# HW_Lab.net
KiCad netlist of a schematic drawn in Altium Designer
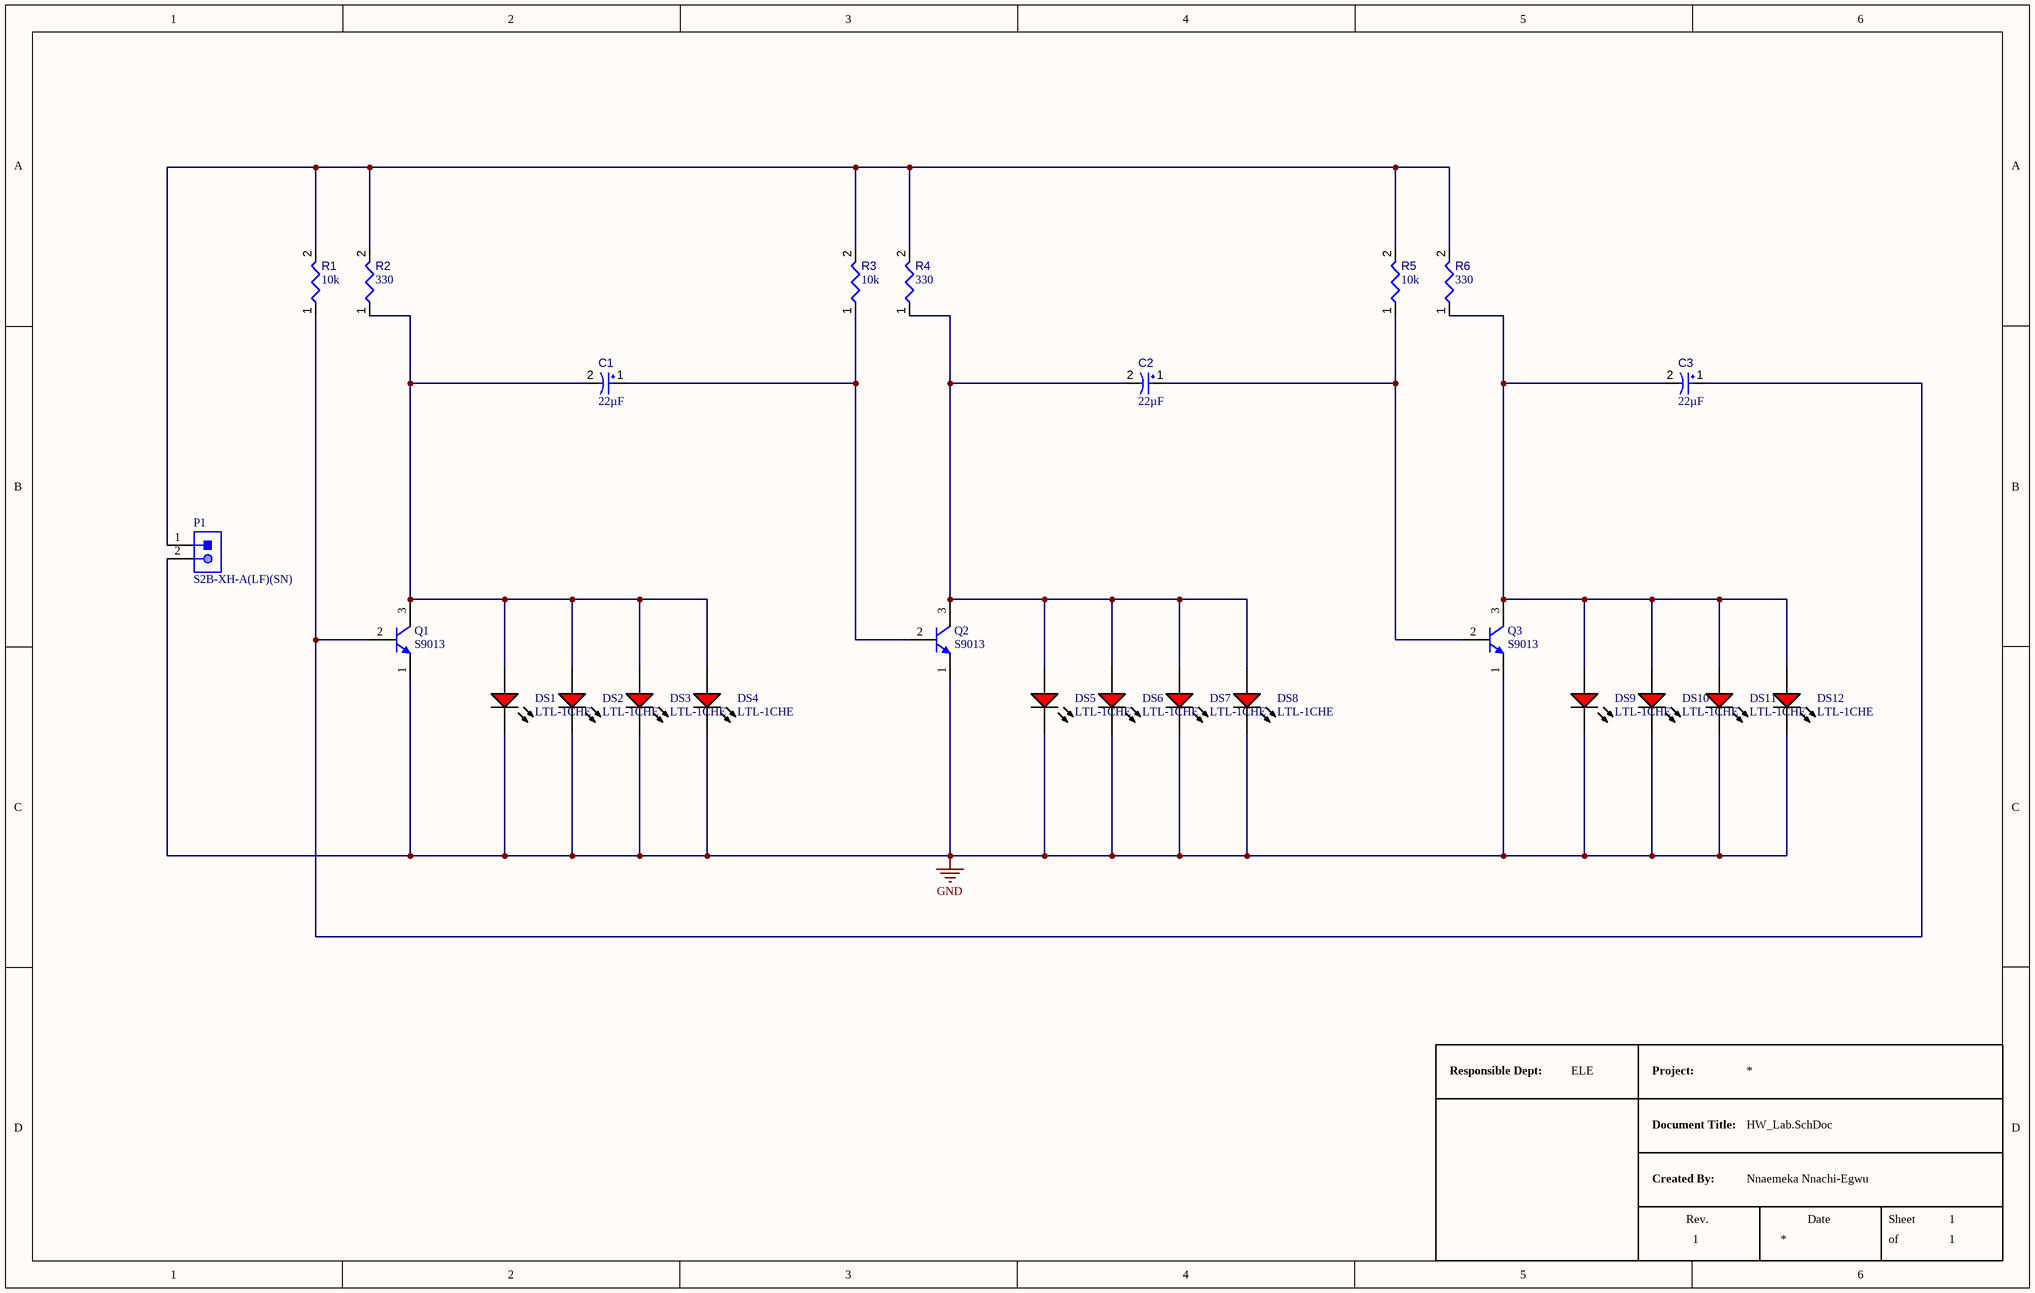
[diagram p0: HW_Lab.SchDoc]

(export (version "E")
  (design (tool "Eeschema 10.0.6"))
  (components
    (comp (ref "*") (value "HSHL_Title_Block") (libsource (lib "Schlib1") (part "HSHL_Title_Block")))
    (comp (ref "C1")
      (value "22µF")
      (footprint "CAPPR55-250-1120X630X1220")
      (description "Aluminum Electrolytic Capacitor, 22 uF, +/- 20%, 100 V, -40 to 85 degC, 2-Pin THD, RoHS, Bulk")
      (fields (field (name "MANUFACTURER") "Panasonic") (field (name "TOLERANCE") "20%"))
      (libsource (lib "Nnaemeka Nnachi-Egwu") (part "CAP-P-2"))
    )
    (comp (ref "C2")
      (value "22µF")
      (footprint "CAPPR55-250-1120X630X1220")
      (description "Aluminum Electrolytic Capacitor, 22 uF, +/- 20%, 100 V, -40 to 85 degC, 2-Pin THD, RoHS, Bulk")
      (fields (field (name "MANUFACTURER") "Panasonic") (field (name "TOLERANCE") "20%"))
      (libsource (lib "Nnaemeka Nnachi-Egwu") (part "CAP-P-2"))
    )
    (comp (ref "C3")
      (value "22µF")
      (footprint "CAPPR55-250-1120X630X1220")
      (description "Aluminum Electrolytic Capacitor, 22 uF, +/- 20%, 100 V, -40 to 85 degC, 2-Pin THD, RoHS, Bulk")
      (fields (field (name "MANUFACTURER") "Panasonic") (field (name "TOLERANCE") "20%"))
      (libsource (lib "Nnaemeka Nnachi-Egwu") (part "CAP-P-2"))
    )
    (comp (ref "DS1")
      (value "LTL-1CHE")
      (footprint "INDPR60-254-520X380X650")
      (description "LED Uni-Color Red, 100 mW, 30 mA, -55 to 100 degC, 2-Pin THD, RoHS, Bulk")
      (fields (field (name "MANUFACTURER") "Lite-On"))
      (libsource (lib "Nnaemeka Nnachi-Egwu") (part "LED-RED-AK-2"))
    )
    (comp (ref "DS2")
      (value "LTL-1CHE")
      (footprint "INDPR60-254-520X380X650")
      (description "LED Uni-Color Red, 100 mW, 30 mA, -55 to 100 degC, 2-Pin THD, RoHS, Bulk")
      (fields (field (name "MANUFACTURER") "Lite-On"))
      (libsource (lib "Nnaemeka Nnachi-Egwu") (part "LED-RED-AK-2"))
    )
    (comp (ref "DS3")
      (value "LTL-1CHE")
      (footprint "INDPR60-254-520X380X650")
      (description "LED Uni-Color Red, 100 mW, 30 mA, -55 to 100 degC, 2-Pin THD, RoHS, Bulk")
      (fields (field (name "MANUFACTURER") "Lite-On"))
      (libsource (lib "Nnaemeka Nnachi-Egwu") (part "LED-RED-AK-2"))
    )
    (comp (ref "DS4")
      (value "LTL-1CHE")
      (footprint "INDPR60-254-520X380X650")
      (description "LED Uni-Color Red, 100 mW, 30 mA, -55 to 100 degC, 2-Pin THD, RoHS, Bulk")
      (fields (field (name "MANUFACTURER") "Lite-On"))
      (libsource (lib "Nnaemeka Nnachi-Egwu") (part "LED-RED-AK-2"))
    )
    (comp (ref "DS5")
      (value "LTL-1CHE")
      (footprint "INDPR60-254-520X380X650")
      (description "LED Uni-Color Red, 100 mW, 30 mA, -55 to 100 degC, 2-Pin THD, RoHS, Bulk")
      (fields (field (name "MANUFACTURER") "Lite-On"))
      (libsource (lib "Nnaemeka Nnachi-Egwu") (part "LED-RED-AK-2"))
    )
    (comp (ref "DS6")
      (value "LTL-1CHE")
      (footprint "INDPR60-254-520X380X650")
      (description "LED Uni-Color Red, 100 mW, 30 mA, -55 to 100 degC, 2-Pin THD, RoHS, Bulk")
      (fields (field (name "MANUFACTURER") "Lite-On"))
      (libsource (lib "Nnaemeka Nnachi-Egwu") (part "LED-RED-AK-2"))
    )
    (comp (ref "DS7")
      (value "LTL-1CHE")
      (footprint "INDPR60-254-520X380X650")
      (description "LED Uni-Color Red, 100 mW, 30 mA, -55 to 100 degC, 2-Pin THD, RoHS, Bulk")
      (fields (field (name "MANUFACTURER") "Lite-On"))
      (libsource (lib "Nnaemeka Nnachi-Egwu") (part "LED-RED-AK-2"))
    )
    (comp (ref "DS8")
      (value "LTL-1CHE")
      (footprint "INDPR60-254-520X380X650")
      (description "LED Uni-Color Red, 100 mW, 30 mA, -55 to 100 degC, 2-Pin THD, RoHS, Bulk")
      (fields (field (name "MANUFACTURER") "Lite-On"))
      (libsource (lib "Nnaemeka Nnachi-Egwu") (part "LED-RED-AK-2"))
    )
    (comp (ref "DS9")
      (value "LTL-1CHE")
      (footprint "INDPR60-254-520X380X650")
      (description "LED Uni-Color Red, 100 mW, 30 mA, -55 to 100 degC, 2-Pin THD, RoHS, Bulk")
      (fields (field (name "MANUFACTURER") "Lite-On"))
      (libsource (lib "Nnaemeka Nnachi-Egwu") (part "LED-RED-AK-2"))
    )
    (comp (ref "DS10")
      (value "LTL-1CHE")
      (footprint "INDPR60-254-520X380X650")
      (description "LED Uni-Color Red, 100 mW, 30 mA, -55 to 100 degC, 2-Pin THD, RoHS, Bulk")
      (fields (field (name "MANUFACTURER") "Lite-On"))
      (libsource (lib "Nnaemeka Nnachi-Egwu") (part "LED-RED-AK-2"))
    )
    (comp (ref "DS11")
      (value "LTL-1CHE")
      (footprint "INDPR60-254-520X380X650")
      (description "LED Uni-Color Red, 100 mW, 30 mA, -55 to 100 degC, 2-Pin THD, RoHS, Bulk")
      (fields (field (name "MANUFACTURER") "Lite-On"))
      (libsource (lib "Nnaemeka Nnachi-Egwu") (part "LED-RED-AK-2"))
    )
    (comp (ref "DS12")
      (value "LTL-1CHE")
      (footprint "INDPR60-254-520X380X650")
      (description "LED Uni-Color Red, 100 mW, 30 mA, -55 to 100 degC, 2-Pin THD, RoHS, Bulk")
      (fields (field (name "MANUFACTURER") "Lite-On"))
      (libsource (lib "Nnaemeka Nnachi-Egwu") (part "LED-RED-AK-2"))
    )
    (comp (ref "P1")
      (value "S2B-XH-A(LF)(SN)")
      (footprint "JST-S2B-XH-A(LF)(SN)_V")
      (fields (field (name "MANUFACTURER") "JST"))
      (libsource (lib "Nnaemeka Nnachi-Egwu") (part "CN-1P-M-R2"))
    )
    (comp (ref "Q1")
      (value "S9013")
      (footprint "JSCJ-TO-92-3_V")
      (description "Transistor, NPN, 0.1 uA, 150 MHz, 3-Pin TO-92")
      (fields (field (name "MANUFACTURER") "Jiangsu Changjiang Electronics Technology"))
      (libsource (lib "Nnaemeka Nnachi-Egwu") (part "BJT-NPN-EBC-3"))
    )
    (comp (ref "Q2")
      (value "S9013")
      (footprint "JSCJ-TO-92-3_V")
      (description "Transistor, NPN, 0.1 uA, 150 MHz, 3-Pin TO-92")
      (fields (field (name "MANUFACTURER") "Jiangsu Changjiang Electronics Technology"))
      (libsource (lib "Nnaemeka Nnachi-Egwu") (part "BJT-NPN-EBC-3"))
    )
    (comp (ref "Q3")
      (value "S9013")
      (footprint "JSCJ-TO-92-3_V")
      (description "Transistor, NPN, 0.1 uA, 150 MHz, 3-Pin TO-92")
      (fields (field (name "MANUFACTURER") "Jiangsu Changjiang Electronics Technology"))
      (libsource (lib "Nnaemeka Nnachi-Egwu") (part "BJT-NPN-EBC-3"))
    )
    (comp (ref "R1")
      (value "10k")
      (footprint "RESA60-630X240")
      (description "Axial Resistor, 10 KOhm, +/- 1%, 0.25 W, -55 to 155 degC, 2-Pin THD, RoHS, Bulk")
      (fields (field (name "TOLERANCE") "1%") (field (name "POWER") "250mW"))
      (libsource (lib "Nnaemeka Nnachi-Egwu") (part "RES-2"))
    )
    (comp (ref "R2")
      (value "330")
      (footprint "STA_CF18_STP")
      (description "Fixed Resistor, Carbon Film, 0.125W, 330ohm, 250V, 5% +/-Tol, -400, 0ppm/Cel, Through Hole Mount")
      (fields (field (name "TOLERANCE") "5%") (field (name "Comment") "CF18JT330R"))
      (libsource (lib "Nnaemeka Nnachi-Egwu") (part "RES-2"))
    )
    (comp (ref "R3")
      (value "10k")
      (footprint "RESA60-630X240")
      (description "Axial Resistor, 10 KOhm, +/- 1%, 0.25 W, -55 to 155 degC, 2-Pin THD, RoHS, Bulk")
      (fields (field (name "TOLERANCE") "1%") (field (name "POWER") "250mW"))
      (libsource (lib "Nnaemeka Nnachi-Egwu") (part "RES-2"))
    )
    (comp (ref "R4")
      (value "330")
      (footprint "STA_CF18_STP")
      (description "Fixed Resistor, Carbon Film, 0.125W, 330ohm, 250V, 5% +/-Tol, -400, 0ppm/Cel, Through Hole Mount")
      (fields (field (name "TOLERANCE") "5%") (field (name "Comment") "CF18JT330R"))
      (libsource (lib "Nnaemeka Nnachi-Egwu") (part "RES-2"))
    )
    (comp (ref "R5")
      (value "10k")
      (footprint "RESA60-630X240")
      (description "Axial Resistor, 10 KOhm, +/- 1%, 0.25 W, -55 to 155 degC, 2-Pin THD, RoHS, Bulk")
      (fields (field (name "TOLERANCE") "1%") (field (name "POWER") "250mW"))
      (libsource (lib "Nnaemeka Nnachi-Egwu") (part "RES-2"))
    )
    (comp (ref "R6")
      (value "330")
      (footprint "STA_CF18_STP")
      (description "Fixed Resistor, Carbon Film, 0.125W, 330ohm, 250V, 5% +/-Tol, -400, 0ppm/Cel, Through Hole Mount")
      (fields (field (name "TOLERANCE") "5%") (field (name "Comment") "CF18JT330R"))
      (libsource (lib "Nnaemeka Nnachi-Egwu") (part "RES-2"))
    )
  )
  (nets
    (net (code "1") (name "GND") (class "Default")
      (node (ref "DS1") (pin "2") (pinfunction "K_2") (pintype "passive"))
      (node (ref "DS10") (pin "2") (pinfunction "K_2") (pintype "passive"))
      (node (ref "DS11") (pin "2") (pinfunction "K_2") (pintype "passive"))
      (node (ref "DS12") (pin "2") (pinfunction "K_2") (pintype "passive"))
      (node (ref "DS2") (pin "2") (pinfunction "K_2") (pintype "passive"))
      (node (ref "DS3") (pin "2") (pinfunction "K_2") (pintype "passive"))
      (node (ref "DS4") (pin "2") (pinfunction "K_2") (pintype "passive"))
      (node (ref "DS5") (pin "2") (pinfunction "K_2") (pintype "passive"))
      (node (ref "DS6") (pin "2") (pinfunction "K_2") (pintype "passive"))
      (node (ref "DS7") (pin "2") (pinfunction "K_2") (pintype "passive"))
      (node (ref "DS8") (pin "2") (pinfunction "K_2") (pintype "passive"))
      (node (ref "DS9") (pin "2") (pinfunction "K_2") (pintype "passive"))
      (node (ref "P1") (pin "2") (pinfunction "2_2") (pintype "passive"))
      (node (ref "Q1") (pin "1") (pinfunction "E_1") (pintype "passive"))
      (node (ref "Q2") (pin "1") (pinfunction "E_1") (pintype "passive"))
      (node (ref "Q3") (pin "1") (pinfunction "E_1") (pintype "passive"))
    )
    (net (code "2") (name "Net-(DS1-A)") (class "Default")
      (node (ref "C1") (pin "2") (pinfunction "2_2") (pintype "passive"))
      (node (ref "DS1") (pin "1") (pinfunction "A_1") (pintype "passive"))
      (node (ref "DS2") (pin "1") (pinfunction "A_1") (pintype "passive"))
      (node (ref "DS3") (pin "1") (pinfunction "A_1") (pintype "passive"))
      (node (ref "DS4") (pin "1") (pinfunction "A_1") (pintype "passive"))
      (node (ref "Q1") (pin "3") (pinfunction "C_3") (pintype "passive"))
      (node (ref "R2") (pin "1") (pinfunction "1_1") (pintype "passive"))
    )
    (net (code "3") (name "Net-(DS5-A)") (class "Default")
      (node (ref "C2") (pin "2") (pinfunction "2_2") (pintype "passive"))
      (node (ref "DS5") (pin "1") (pinfunction "A_1") (pintype "passive"))
      (node (ref "DS6") (pin "1") (pinfunction "A_1") (pintype "passive"))
      (node (ref "DS7") (pin "1") (pinfunction "A_1") (pintype "passive"))
      (node (ref "DS8") (pin "1") (pinfunction "A_1") (pintype "passive"))
      (node (ref "Q2") (pin "3") (pinfunction "C_3") (pintype "passive"))
      (node (ref "R4") (pin "1") (pinfunction "1_1") (pintype "passive"))
    )
    (net (code "4") (name "Net-(DS10-A)") (class "Default")
      (node (ref "C3") (pin "2") (pinfunction "2_2") (pintype "passive"))
      (node (ref "DS10") (pin "1") (pinfunction "A_1") (pintype "passive"))
      (node (ref "DS11") (pin "1") (pinfunction "A_1") (pintype "passive"))
      (node (ref "DS12") (pin "1") (pinfunction "A_1") (pintype "passive"))
      (node (ref "DS9") (pin "1") (pinfunction "A_1") (pintype "passive"))
      (node (ref "Q3") (pin "3") (pinfunction "C_3") (pintype "passive"))
      (node (ref "R6") (pin "1") (pinfunction "1_1") (pintype "passive"))
    )
    (net (code "5") (name "Net-(P1-Pad1)") (class "Default")
      (node (ref "P1") (pin "1") (pinfunction "1_1") (pintype "passive"))
      (node (ref "R1") (pin "2") (pinfunction "2_2") (pintype "passive"))
      (node (ref "R2") (pin "2") (pinfunction "2_2") (pintype "passive"))
      (node (ref "R3") (pin "2") (pinfunction "2_2") (pintype "passive"))
      (node (ref "R4") (pin "2") (pinfunction "2_2") (pintype "passive"))
      (node (ref "R5") (pin "2") (pinfunction "2_2") (pintype "passive"))
      (node (ref "R6") (pin "2") (pinfunction "2_2") (pintype "passive"))
    )
    (net (code "6") (name "Net-(Q1-B)") (class "Default")
      (node (ref "C3") (pin "1") (pinfunction "1_1") (pintype "passive"))
      (node (ref "Q1") (pin "2") (pinfunction "B_2") (pintype "passive"))
      (node (ref "R1") (pin "1") (pinfunction "1_1") (pintype "passive"))
    )
    (net (code "7") (name "Net-(Q2-B)") (class "Default")
      (node (ref "C1") (pin "1") (pinfunction "1_1") (pintype "passive"))
      (node (ref "Q2") (pin "2") (pinfunction "B_2") (pintype "passive"))
      (node (ref "R3") (pin "1") (pinfunction "1_1") (pintype "passive"))
    )
    (net (code "8") (name "Net-(Q3-B)") (class "Default")
      (node (ref "C2") (pin "1") (pinfunction "1_1") (pintype "passive"))
      (node (ref "Q3") (pin "2") (pinfunction "B_2") (pintype "passive"))
      (node (ref "R5") (pin "1") (pinfunction "1_1") (pintype "passive"))
    )
  )
)
